# CameraController.net
KiCad netlist of a schematic drawn in EAGLE
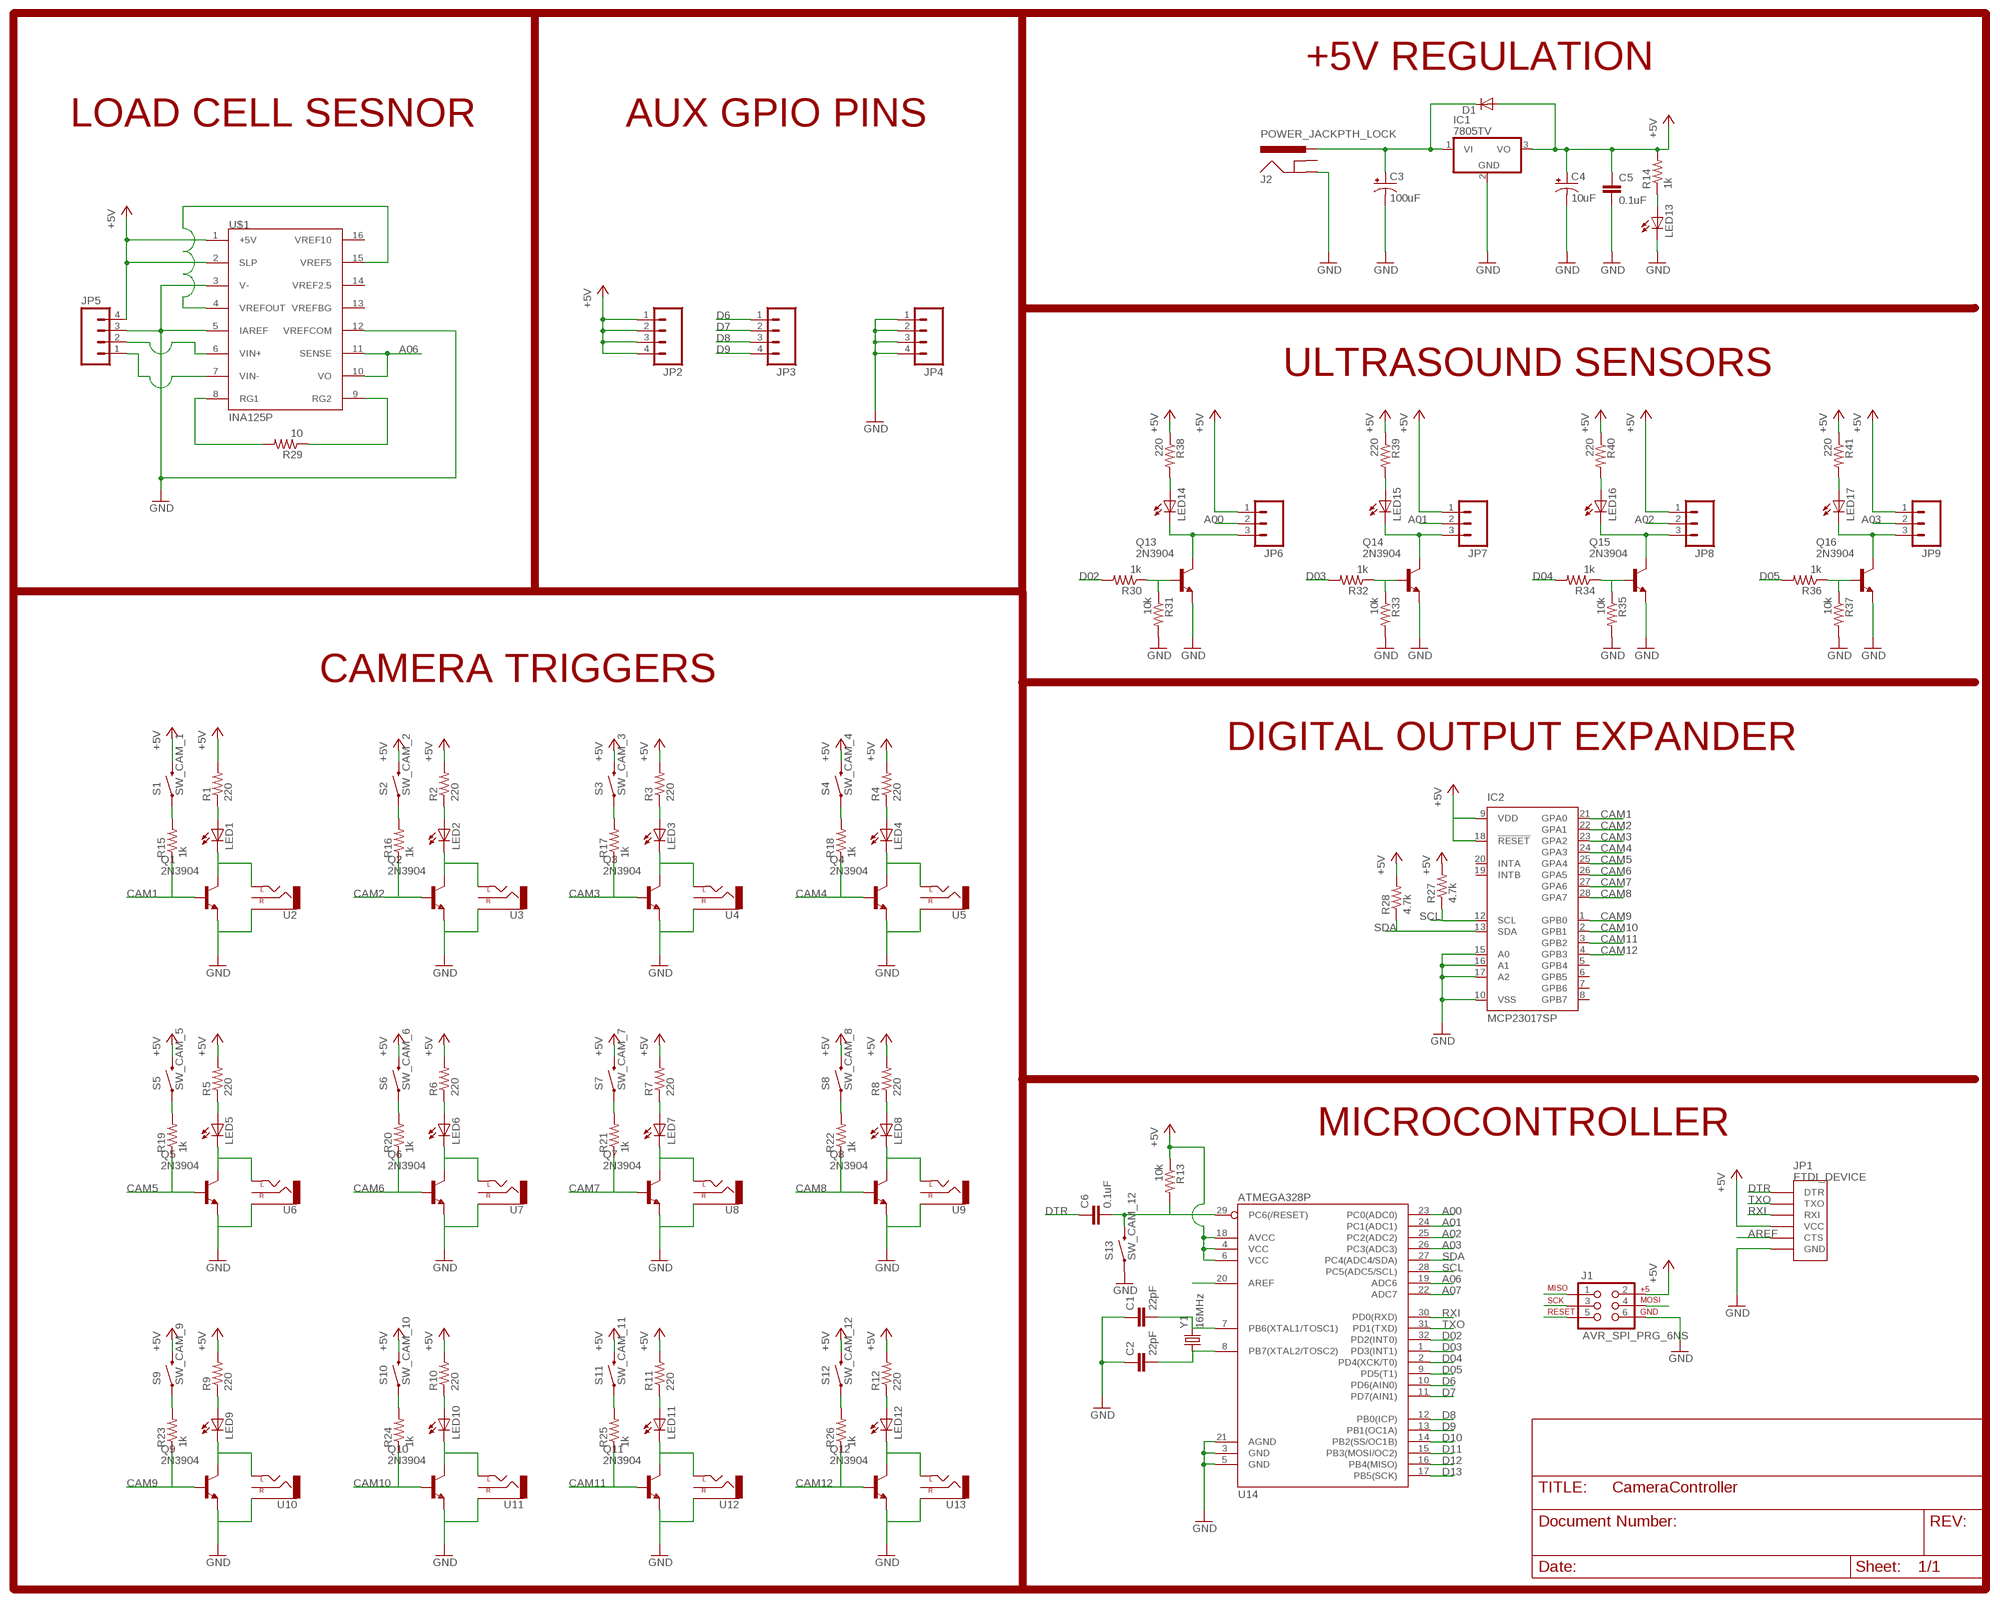
[diagram p0: schematic, sheet 1]

(export (version "E")
  (design (tool "Eeschema 10.0.6"))
  (components
    (comp (ref "C1")
      (value "22pF")
      (footprint "eagle-import:CAP-PTH-SMALL2")
      (libsource (lib "eagle-import") (part "CAPPTH2"))
    )
    (comp (ref "C2")
      (value "22pF")
      (footprint "eagle-import:CAP-PTH-SMALL2")
      (libsource (lib "eagle-import") (part "CAPPTH2"))
    )
    (comp (ref "C3")
      (value "100uF")
      (footprint "eagle-import:E2,5-7")
      (libsource (lib "eagle-import") (part "CPOL-USE2.5-7"))
    )
    (comp (ref "C4")
      (value "10uF")
      (footprint "eagle-import:E2,5-5")
      (libsource (lib "eagle-import") (part "CPOL-USE2.5-5"))
    )
    (comp (ref "C5")
      (value "0.1uF")
      (footprint "eagle-import:C025-025X050")
      (libsource (lib "eagle-import") (part "C-EU025-025X050"))
    )
    (comp (ref "C6")
      (value "0.1uF")
      (footprint "eagle-import:C025-025X050")
      (libsource (lib "eagle-import") (part "C-EU025-025X050"))
    )
    (comp (ref "D1")
      (value "DIODEPTH")
      (footprint "eagle-import:DIODE-1N4001")
      (libsource (lib "eagle-import") (part "DIODEPTH"))
    )
    (comp (ref "IC1")
      (value "7805TV")
      (footprint "eagle-import:TO220V")
      (libsource (lib "eagle-import") (part "78TV05"))
    )
    (comp (ref "IC2")
      (value "MCP23017SP")
      (footprint "eagle-import:DIL28-3")
      (libsource (lib "eagle-import") (part "MCP23017SP"))
    )
    (comp (ref "J1")
      (value "AVR_SPI_PRG_6NS")
      (footprint "eagle-import:2X3-NS")
      (libsource (lib "eagle-import") (part "AVR_SPI_PRG_6NS"))
    )
    (comp (ref "J2")
      (value "POWER_JACKPTH_LOCK")
      (footprint "eagle-import:POWER_JACK_PTH_LOCK")
      (libsource (lib "eagle-import") (part "POWER_JACKPTH_LOCK"))
    )
    (comp (ref "JP1")
      (value "FTDI_DEVICE")
      (footprint "eagle-import:FTDI_DEVICE_SIDE")
      (libsource (lib "eagle-import") (part "FTDI_DEVICE"))
    )
    (comp (ref "JP2")
      (value "M04PTH")
      (footprint "eagle-import:1X04")
      (libsource (lib "eagle-import") (part "M04PTH"))
    )
    (comp (ref "JP3")
      (value "M04PTH")
      (footprint "eagle-import:1X04")
      (libsource (lib "eagle-import") (part "M04PTH"))
    )
    (comp (ref "JP4")
      (value "M04PTH")
      (footprint "eagle-import:1X04")
      (libsource (lib "eagle-import") (part "M04PTH"))
    )
    (comp (ref "JP5")
      (value "M04LONGPADS")
      (footprint "eagle-import:1X04_LONGPADS")
      (libsource (lib "eagle-import") (part "M04LONGPADS"))
    )
    (comp (ref "JP6")
      (value "M03LONGPADS")
      (footprint "eagle-import:1X03_LONGPADS")
      (libsource (lib "eagle-import") (part "M03LONGPADS"))
    )
    (comp (ref "JP7")
      (value "M03LONGPADS")
      (footprint "eagle-import:1X03_LONGPADS")
      (libsource (lib "eagle-import") (part "M03LONGPADS"))
    )
    (comp (ref "JP8")
      (value "M03LONGPADS")
      (footprint "eagle-import:1X03_LONGPADS")
      (libsource (lib "eagle-import") (part "M03LONGPADS"))
    )
    (comp (ref "JP9")
      (value "M03LONGPADS")
      (footprint "eagle-import:1X03_LONGPADS")
      (libsource (lib "eagle-import") (part "M03LONGPADS"))
    )
    (comp (ref "LED1")
      (value "LED5MM")
      (footprint "eagle-import:LED5MM")
      (libsource (lib "eagle-import") (part "LED5MM"))
    )
    (comp (ref "LED2")
      (value "LED5MM")
      (footprint "eagle-import:LED5MM")
      (libsource (lib "eagle-import") (part "LED5MM"))
    )
    (comp (ref "LED3")
      (value "LED5MM")
      (footprint "eagle-import:LED5MM")
      (libsource (lib "eagle-import") (part "LED5MM"))
    )
    (comp (ref "LED4")
      (value "LED5MM")
      (footprint "eagle-import:LED5MM")
      (libsource (lib "eagle-import") (part "LED5MM"))
    )
    (comp (ref "LED5")
      (value "LED5MM")
      (footprint "eagle-import:LED5MM")
      (libsource (lib "eagle-import") (part "LED5MM"))
    )
    (comp (ref "LED6")
      (value "LED5MM")
      (footprint "eagle-import:LED5MM")
      (libsource (lib "eagle-import") (part "LED5MM"))
    )
    (comp (ref "LED7")
      (value "LED5MM")
      (footprint "eagle-import:LED5MM")
      (libsource (lib "eagle-import") (part "LED5MM"))
    )
    (comp (ref "LED8")
      (value "LED5MM")
      (footprint "eagle-import:LED5MM")
      (libsource (lib "eagle-import") (part "LED5MM"))
    )
    (comp (ref "LED9")
      (value "LED5MM")
      (footprint "eagle-import:LED5MM")
      (libsource (lib "eagle-import") (part "LED5MM"))
    )
    (comp (ref "LED10")
      (value "LED5MM")
      (footprint "eagle-import:LED5MM")
      (libsource (lib "eagle-import") (part "LED5MM"))
    )
    (comp (ref "LED11")
      (value "LED5MM")
      (footprint "eagle-import:LED5MM")
      (libsource (lib "eagle-import") (part "LED5MM"))
    )
    (comp (ref "LED12")
      (value "LED5MM")
      (footprint "eagle-import:LED5MM")
      (libsource (lib "eagle-import") (part "LED5MM"))
    )
    (comp (ref "LED13")
      (value "LED5MM")
      (footprint "eagle-import:LED5MM")
      (libsource (lib "eagle-import") (part "LED5MM"))
    )
    (comp (ref "LED14")
      (value "LED5MM")
      (footprint "eagle-import:LED5MM")
      (libsource (lib "eagle-import") (part "LED5MM"))
    )
    (comp (ref "LED15")
      (value "LED5MM")
      (footprint "eagle-import:LED5MM")
      (libsource (lib "eagle-import") (part "LED5MM"))
    )
    (comp (ref "LED16")
      (value "LED5MM")
      (footprint "eagle-import:LED5MM")
      (libsource (lib "eagle-import") (part "LED5MM"))
    )
    (comp (ref "LED17")
      (value "LED5MM")
      (footprint "eagle-import:LED5MM")
      (libsource (lib "eagle-import") (part "LED5MM"))
    )
    (comp (ref "Q1")
      (value "2N3904")
      (footprint "eagle-import:TO92")
      (libsource (lib "eagle-import") (part "2N3904"))
    )
    (comp (ref "Q2")
      (value "2N3904")
      (footprint "eagle-import:TO92")
      (libsource (lib "eagle-import") (part "2N3904"))
    )
    (comp (ref "Q3")
      (value "2N3904")
      (footprint "eagle-import:TO92")
      (libsource (lib "eagle-import") (part "2N3904"))
    )
    (comp (ref "Q4")
      (value "2N3904")
      (footprint "eagle-import:TO92")
      (libsource (lib "eagle-import") (part "2N3904"))
    )
    (comp (ref "Q5")
      (value "2N3904")
      (footprint "eagle-import:TO92")
      (libsource (lib "eagle-import") (part "2N3904"))
    )
    (comp (ref "Q6")
      (value "2N3904")
      (footprint "eagle-import:TO92")
      (libsource (lib "eagle-import") (part "2N3904"))
    )
    (comp (ref "Q7")
      (value "2N3904")
      (footprint "eagle-import:TO92")
      (libsource (lib "eagle-import") (part "2N3904"))
    )
    (comp (ref "Q8")
      (value "2N3904")
      (footprint "eagle-import:TO92")
      (libsource (lib "eagle-import") (part "2N3904"))
    )
    (comp (ref "Q9")
      (value "2N3904")
      (footprint "eagle-import:TO92")
      (libsource (lib "eagle-import") (part "2N3904"))
    )
    (comp (ref "Q10")
      (value "2N3904")
      (footprint "eagle-import:TO92")
      (libsource (lib "eagle-import") (part "2N3904"))
    )
    (comp (ref "Q11")
      (value "2N3904")
      (footprint "eagle-import:TO92")
      (libsource (lib "eagle-import") (part "2N3904"))
    )
    (comp (ref "Q12")
      (value "2N3904")
      (footprint "eagle-import:TO92")
      (libsource (lib "eagle-import") (part "2N3904"))
    )
    (comp (ref "Q13")
      (value "2N3904")
      (footprint "eagle-import:TO92")
      (libsource (lib "eagle-import") (part "2N3904"))
    )
    (comp (ref "Q14")
      (value "2N3904")
      (footprint "eagle-import:TO92")
      (libsource (lib "eagle-import") (part "2N3904"))
    )
    (comp (ref "Q15")
      (value "2N3904")
      (footprint "eagle-import:TO92")
      (libsource (lib "eagle-import") (part "2N3904"))
    )
    (comp (ref "Q16")
      (value "2N3904")
      (footprint "eagle-import:TO92")
      (libsource (lib "eagle-import") (part "2N3904"))
    )
    (comp (ref "R1")
      (value "220")
      (footprint "eagle-import:0207_10")
      (libsource (lib "eagle-import") (part "R-US_0207/10"))
    )
    (comp (ref "R2")
      (value "220")
      (footprint "eagle-import:0207_10")
      (libsource (lib "eagle-import") (part "R-US_0207/10"))
    )
    (comp (ref "R3")
      (value "220")
      (footprint "eagle-import:0207_10")
      (libsource (lib "eagle-import") (part "R-US_0207/10"))
    )
    (comp (ref "R4")
      (value "220")
      (footprint "eagle-import:0207_10")
      (libsource (lib "eagle-import") (part "R-US_0207/10"))
    )
    (comp (ref "R5")
      (value "220")
      (footprint "eagle-import:0207_10")
      (libsource (lib "eagle-import") (part "R-US_0207/10"))
    )
    (comp (ref "R6")
      (value "220")
      (footprint "eagle-import:0207_10")
      (libsource (lib "eagle-import") (part "R-US_0207/10"))
    )
    (comp (ref "R7")
      (value "220")
      (footprint "eagle-import:0207_10")
      (libsource (lib "eagle-import") (part "R-US_0207/10"))
    )
    (comp (ref "R8")
      (value "220")
      (footprint "eagle-import:0207_10")
      (libsource (lib "eagle-import") (part "R-US_0207/10"))
    )
    (comp (ref "R9")
      (value "220")
      (footprint "eagle-import:0207_10")
      (libsource (lib "eagle-import") (part "R-US_0207/10"))
    )
    (comp (ref "R10")
      (value "220")
      (footprint "eagle-import:0207_10")
      (libsource (lib "eagle-import") (part "R-US_0207/10"))
    )
    (comp (ref "R11")
      (value "220")
      (footprint "eagle-import:0207_10")
      (libsource (lib "eagle-import") (part "R-US_0207/10"))
    )
    (comp (ref "R12")
      (value "220")
      (footprint "eagle-import:0207_10")
      (libsource (lib "eagle-import") (part "R-US_0207/10"))
    )
    (comp (ref "R13")
      (value "10k")
      (footprint "eagle-import:0207_10")
      (libsource (lib "eagle-import") (part "R-US_0207/10"))
    )
    (comp (ref "R14")
      (value "1k")
      (footprint "eagle-import:0207_10")
      (libsource (lib "eagle-import") (part "R-US_0207/10"))
    )
    (comp (ref "R15")
      (value "1k")
      (footprint "eagle-import:0207_10")
      (libsource (lib "eagle-import") (part "R-US_0207/10"))
    )
    (comp (ref "R16")
      (value "1k")
      (footprint "eagle-import:0207_10")
      (libsource (lib "eagle-import") (part "R-US_0207/10"))
    )
    (comp (ref "R17")
      (value "1k")
      (footprint "eagle-import:0207_10")
      (libsource (lib "eagle-import") (part "R-US_0207/10"))
    )
    (comp (ref "R18")
      (value "1k")
      (footprint "eagle-import:0207_10")
      (libsource (lib "eagle-import") (part "R-US_0207/10"))
    )
    (comp (ref "R19")
      (value "1k")
      (footprint "eagle-import:0207_10")
      (libsource (lib "eagle-import") (part "R-US_0207/10"))
    )
    (comp (ref "R20")
      (value "1k")
      (footprint "eagle-import:0207_10")
      (libsource (lib "eagle-import") (part "R-US_0207/10"))
    )
    (comp (ref "R21")
      (value "1k")
      (footprint "eagle-import:0207_10")
      (libsource (lib "eagle-import") (part "R-US_0207/10"))
    )
    (comp (ref "R22")
      (value "1k")
      (footprint "eagle-import:0207_10")
      (libsource (lib "eagle-import") (part "R-US_0207/10"))
    )
    (comp (ref "R23")
      (value "1k")
      (footprint "eagle-import:0207_10")
      (libsource (lib "eagle-import") (part "R-US_0207/10"))
    )
    (comp (ref "R24")
      (value "1k")
      (footprint "eagle-import:0207_10")
      (libsource (lib "eagle-import") (part "R-US_0207/10"))
    )
    (comp (ref "R25")
      (value "1k")
      (footprint "eagle-import:0207_10")
      (libsource (lib "eagle-import") (part "R-US_0207/10"))
    )
    (comp (ref "R26")
      (value "1k")
      (footprint "eagle-import:0207_10")
      (libsource (lib "eagle-import") (part "R-US_0207/10"))
    )
    (comp (ref "R27")
      (value "4.7k")
      (footprint "eagle-import:0207_10")
      (libsource (lib "eagle-import") (part "R-US_0207/10"))
    )
    (comp (ref "R28")
      (value "4.7k")
      (footprint "eagle-import:0207_10")
      (libsource (lib "eagle-import") (part "R-US_0207/10"))
    )
    (comp (ref "R29")
      (value "10")
      (footprint "eagle-import:0207_10")
      (libsource (lib "eagle-import") (part "R-US_0207/10"))
    )
    (comp (ref "R30")
      (value "1k")
      (footprint "eagle-import:0207_10")
      (libsource (lib "eagle-import") (part "R-US_0207/10"))
    )
    (comp (ref "R31")
      (value "10k")
      (footprint "eagle-import:0207_10")
      (libsource (lib "eagle-import") (part "R-US_0207/10"))
    )
    (comp (ref "R32")
      (value "1k")
      (footprint "eagle-import:0207_10")
      (libsource (lib "eagle-import") (part "R-US_0207/10"))
    )
    (comp (ref "R33")
      (value "10k")
      (footprint "eagle-import:0207_10")
      (libsource (lib "eagle-import") (part "R-US_0207/10"))
    )
    (comp (ref "R34")
      (value "1k")
      (footprint "eagle-import:0207_10")
      (libsource (lib "eagle-import") (part "R-US_0207/10"))
    )
    (comp (ref "R35")
      (value "10k")
      (footprint "eagle-import:0207_10")
      (libsource (lib "eagle-import") (part "R-US_0207/10"))
    )
    (comp (ref "R36")
      (value "1k")
      (footprint "eagle-import:0207_10")
      (libsource (lib "eagle-import") (part "R-US_0207/10"))
    )
    (comp (ref "R37")
      (value "10k")
      (footprint "eagle-import:0207_10")
      (libsource (lib "eagle-import") (part "R-US_0207/10"))
    )
    (comp (ref "R38")
      (value "220")
      (footprint "eagle-import:0207_10")
      (libsource (lib "eagle-import") (part "R-US_0207/10"))
    )
    (comp (ref "R39")
      (value "220")
      (footprint "eagle-import:0207_10")
      (libsource (lib "eagle-import") (part "R-US_0207/10"))
    )
    (comp (ref "R40")
      (value "220")
      (footprint "eagle-import:0207_10")
      (libsource (lib "eagle-import") (part "R-US_0207/10"))
    )
    (comp (ref "R41")
      (value "220")
      (footprint "eagle-import:0207_10")
      (libsource (lib "eagle-import") (part "R-US_0207/10"))
    )
    (comp (ref "S1")
      (value "SW_CAM_1")
      (footprint "eagle-import:TACTILE-PTH")
      (libsource (lib "eagle-import") (part "SWITCH-MOMENTARY-2PTH"))
    )
    (comp (ref "S2")
      (value "SW_CAM_2")
      (footprint "eagle-import:TACTILE-PTH")
      (libsource (lib "eagle-import") (part "SWITCH-MOMENTARY-2PTH"))
    )
    (comp (ref "S3")
      (value "SW_CAM_3")
      (footprint "eagle-import:TACTILE-PTH")
      (libsource (lib "eagle-import") (part "SWITCH-MOMENTARY-2PTH"))
    )
    (comp (ref "S4")
      (value "SW_CAM_4")
      (footprint "eagle-import:TACTILE-PTH")
      (libsource (lib "eagle-import") (part "SWITCH-MOMENTARY-2PTH"))
    )
    (comp (ref "S5")
      (value "SW_CAM_5")
      (footprint "eagle-import:TACTILE-PTH")
      (libsource (lib "eagle-import") (part "SWITCH-MOMENTARY-2PTH"))
    )
    (comp (ref "S6")
      (value "SW_CAM_6")
      (footprint "eagle-import:TACTILE-PTH")
      (libsource (lib "eagle-import") (part "SWITCH-MOMENTARY-2PTH"))
    )
    (comp (ref "S7")
      (value "SW_CAM_7")
      (footprint "eagle-import:TACTILE-PTH")
      (libsource (lib "eagle-import") (part "SWITCH-MOMENTARY-2PTH"))
    )
    (comp (ref "S8")
      (value "SW_CAM_8")
      (footprint "eagle-import:TACTILE-PTH")
      (libsource (lib "eagle-import") (part "SWITCH-MOMENTARY-2PTH"))
    )
    (comp (ref "S9")
      (value "SW_CAM_9")
      (footprint "eagle-import:TACTILE-PTH")
      (libsource (lib "eagle-import") (part "SWITCH-MOMENTARY-2PTH"))
    )
    (comp (ref "S10")
      (value "SW_CAM_10")
      (footprint "eagle-import:TACTILE-PTH")
      (libsource (lib "eagle-import") (part "SWITCH-MOMENTARY-2PTH"))
    )
    (comp (ref "S11")
      (value "SW_CAM_11")
      (footprint "eagle-import:TACTILE-PTH")
      (libsource (lib "eagle-import") (part "SWITCH-MOMENTARY-2PTH"))
    )
    (comp (ref "S12")
      (value "SW_CAM_12")
      (footprint "eagle-import:TACTILE-PTH")
      (libsource (lib "eagle-import") (part "SWITCH-MOMENTARY-2PTH"))
    )
    (comp (ref "S13")
      (value "SW_CAM_12")
      (footprint "eagle-import:TACTILE-PTH")
      (libsource (lib "eagle-import") (part "SWITCH-MOMENTARY-2PTH"))
    )
    (comp (ref "U$1")
      (value "INA125P")
      (footprint "eagle-import:16-DIP")
      (libsource (lib "eagle-import") (part "INA125P"))
    )
    (comp (ref "U2")
      (value "AUDIO-JACKSPECIAL_POGO_PINS")
      (footprint "eagle-import:STEREOJACK2.5MM_SPECIA_POGOPINS")
      (libsource (lib "eagle-import") (part "AUDIO-JACKSPECIAL_POGO_PINS"))
    )
    (comp (ref "U3")
      (value "AUDIO-JACKSPECIAL_POGO_PINS")
      (footprint "eagle-import:STEREOJACK2.5MM_SPECIA_POGOPINS")
      (libsource (lib "eagle-import") (part "AUDIO-JACKSPECIAL_POGO_PINS"))
    )
    (comp (ref "U4")
      (value "AUDIO-JACKSPECIAL_POGO_PINS")
      (footprint "eagle-import:STEREOJACK2.5MM_SPECIA_POGOPINS")
      (libsource (lib "eagle-import") (part "AUDIO-JACKSPECIAL_POGO_PINS"))
    )
    (comp (ref "U5")
      (value "AUDIO-JACKSPECIAL_POGO_PINS")
      (footprint "eagle-import:STEREOJACK2.5MM_SPECIA_POGOPINS")
      (libsource (lib "eagle-import") (part "AUDIO-JACKSPECIAL_POGO_PINS"))
    )
    (comp (ref "U6")
      (value "AUDIO-JACKSPECIAL_POGO_PINS")
      (footprint "eagle-import:STEREOJACK2.5MM_SPECIA_POGOPINS")
      (libsource (lib "eagle-import") (part "AUDIO-JACKSPECIAL_POGO_PINS"))
    )
    (comp (ref "U7")
      (value "AUDIO-JACKSPECIAL_POGO_PINS")
      (footprint "eagle-import:STEREOJACK2.5MM_SPECIA_POGOPINS")
      (libsource (lib "eagle-import") (part "AUDIO-JACKSPECIAL_POGO_PINS"))
    )
    (comp (ref "U8")
      (value "AUDIO-JACKSPECIAL_POGO_PINS")
      (footprint "eagle-import:STEREOJACK2.5MM_SPECIA_POGOPINS")
      (libsource (lib "eagle-import") (part "AUDIO-JACKSPECIAL_POGO_PINS"))
    )
    (comp (ref "U9")
      (value "AUDIO-JACKSPECIAL_POGO_PINS")
      (footprint "eagle-import:STEREOJACK2.5MM_SPECIA_POGOPINS")
      (libsource (lib "eagle-import") (part "AUDIO-JACKSPECIAL_POGO_PINS"))
    )
    (comp (ref "U10")
      (value "AUDIO-JACKSPECIAL_POGO_PINS")
      (footprint "eagle-import:STEREOJACK2.5MM_SPECIA_POGOPINS")
      (libsource (lib "eagle-import") (part "AUDIO-JACKSPECIAL_POGO_PINS"))
    )
    (comp (ref "U11")
      (value "AUDIO-JACKSPECIAL_POGO_PINS")
      (footprint "eagle-import:STEREOJACK2.5MM_SPECIA_POGOPINS")
      (libsource (lib "eagle-import") (part "AUDIO-JACKSPECIAL_POGO_PINS"))
    )
    (comp (ref "U12")
      (value "AUDIO-JACKSPECIAL_POGO_PINS")
      (footprint "eagle-import:STEREOJACK2.5MM_SPECIA_POGOPINS")
      (libsource (lib "eagle-import") (part "AUDIO-JACKSPECIAL_POGO_PINS"))
    )
    (comp (ref "U13")
      (value "AUDIO-JACKSPECIAL_POGO_PINS")
      (footprint "eagle-import:STEREOJACK2.5MM_SPECIA_POGOPINS")
      (libsource (lib "eagle-import") (part "AUDIO-JACKSPECIAL_POGO_PINS"))
    )
    (comp (ref "U14")
      (value "ATMEGA328P")
      (footprint "eagle-import:TQFP32-08")
      (libsource (lib "eagle-import") (part "ATMEGA328_SMT"))
    )
    (comp (ref "Y1")
      (value "16MHz")
      (footprint "eagle-import:HC49US")
      (libsource (lib "eagle-import") (part "CRYSTALHC49US"))
    )
  )
  (nets
    (net (code "1") (name "+5V") (class "Default")
      (node (ref "C4") (pin "+") (pinfunction "+_+") (pintype "passive"))
      (node (ref "C5") (pin "1") (pinfunction "1_1") (pintype "passive"))
      (node (ref "D1") (pin "A") (pinfunction "A_A") (pintype "passive"))
      (node (ref "IC1") (pin "3") (pinfunction "VO_3") (pintype "passive"))
      (node (ref "IC2") (pin "18") (pinfunction "~{RESET}_18") (pintype "input"))
      (node (ref "IC2") (pin "9") (pinfunction "VDD_9") (pintype "power_in"))
      (node (ref "J1") (pin "2") (pinfunction "2_2") (pintype "passive"))
      (node (ref "JP1") (pin "P$4") (pinfunction "VCC_P$4") (pintype "bidirectional"))
      (node (ref "JP2") (pin "1") (pinfunction "1_1") (pintype "passive"))
      (node (ref "JP2") (pin "2") (pinfunction "2_2") (pintype "passive"))
      (node (ref "JP2") (pin "3") (pinfunction "3_3") (pintype "passive"))
      (node (ref "JP2") (pin "4") (pinfunction "4_4") (pintype "passive"))
      (node (ref "JP5") (pin "4") (pinfunction "4_4") (pintype "passive"))
      (node (ref "JP6") (pin "1") (pinfunction "1_1") (pintype "passive"))
      (node (ref "JP7") (pin "1") (pinfunction "1_1") (pintype "passive"))
      (node (ref "JP8") (pin "1") (pinfunction "1_1") (pintype "passive"))
      (node (ref "JP9") (pin "1") (pinfunction "1_1") (pintype "passive"))
      (node (ref "R1") (pin "2") (pinfunction "2_2") (pintype "passive"))
      (node (ref "R10") (pin "2") (pinfunction "2_2") (pintype "passive"))
      (node (ref "R11") (pin "2") (pinfunction "2_2") (pintype "passive"))
      (node (ref "R12") (pin "2") (pinfunction "2_2") (pintype "passive"))
      (node (ref "R13") (pin "1") (pinfunction "1_1") (pintype "passive"))
      (node (ref "R14") (pin "2") (pinfunction "2_2") (pintype "passive"))
      (node (ref "R2") (pin "2") (pinfunction "2_2") (pintype "passive"))
      (node (ref "R27") (pin "2") (pinfunction "2_2") (pintype "passive"))
      (node (ref "R28") (pin "2") (pinfunction "2_2") (pintype "passive"))
      (node (ref "R3") (pin "2") (pinfunction "2_2") (pintype "passive"))
      (node (ref "R38") (pin "1") (pinfunction "1_1") (pintype "passive"))
      (node (ref "R39") (pin "1") (pinfunction "1_1") (pintype "passive"))
      (node (ref "R4") (pin "2") (pinfunction "2_2") (pintype "passive"))
      (node (ref "R40") (pin "1") (pinfunction "1_1") (pintype "passive"))
      (node (ref "R41") (pin "1") (pinfunction "1_1") (pintype "passive"))
      (node (ref "R5") (pin "2") (pinfunction "2_2") (pintype "passive"))
      (node (ref "R6") (pin "2") (pinfunction "2_2") (pintype "passive"))
      (node (ref "R7") (pin "2") (pinfunction "2_2") (pintype "passive"))
      (node (ref "R8") (pin "2") (pinfunction "2_2") (pintype "passive"))
      (node (ref "R9") (pin "2") (pinfunction "2_2") (pintype "passive"))
      (node (ref "S1") (pin "3") (pinfunction "2_3") (pintype "passive"))
      (node (ref "S10") (pin "3") (pinfunction "2_3") (pintype "passive"))
      (node (ref "S11") (pin "3") (pinfunction "2_3") (pintype "passive"))
      (node (ref "S12") (pin "3") (pinfunction "2_3") (pintype "passive"))
      (node (ref "S2") (pin "3") (pinfunction "2_3") (pintype "passive"))
      (node (ref "S3") (pin "3") (pinfunction "2_3") (pintype "passive"))
      (node (ref "S4") (pin "3") (pinfunction "2_3") (pintype "passive"))
      (node (ref "S5") (pin "3") (pinfunction "2_3") (pintype "passive"))
      (node (ref "S6") (pin "3") (pinfunction "2_3") (pintype "passive"))
      (node (ref "S7") (pin "3") (pinfunction "2_3") (pintype "passive"))
      (node (ref "S8") (pin "3") (pinfunction "2_3") (pintype "passive"))
      (node (ref "S9") (pin "3") (pinfunction "2_3") (pintype "passive"))
      (node (ref "U$1") (pin "1") (pinfunction "+5V_1") (pintype "bidirectional"))
      (node (ref "U$1") (pin "2") (pinfunction "SLP_2") (pintype "bidirectional"))
      (node (ref "U14") (pin "18") (pinfunction "AVCC_18") (pintype "bidirectional"))
      (node (ref "U14") (pin "4") (pinfunction "VCC_4") (pintype "bidirectional"))
      (node (ref "U14") (pin "6") (pinfunction "VCC_6") (pintype "bidirectional"))
    )
    (net (code "2") (name "/A00") (class "Default")
      (node (ref "JP6") (pin "2") (pinfunction "2_2") (pintype "passive"))
      (node (ref "U14") (pin "23") (pinfunction "PC0(ADC0)_23") (pintype "bidirectional"))
    )
    (net (code "3") (name "/A01") (class "Default")
      (node (ref "JP7") (pin "2") (pinfunction "2_2") (pintype "passive"))
      (node (ref "U14") (pin "24") (pinfunction "PC1(ADC1)_24") (pintype "bidirectional"))
    )
    (net (code "4") (name "/A02") (class "Default")
      (node (ref "JP8") (pin "2") (pinfunction "2_2") (pintype "passive"))
      (node (ref "U14") (pin "25") (pinfunction "PC2(ADC2)_25") (pintype "bidirectional"))
    )
    (net (code "5") (name "/A03") (class "Default")
      (node (ref "JP9") (pin "2") (pinfunction "2_2") (pintype "passive"))
      (node (ref "U14") (pin "26") (pinfunction "PC3(ADC3)_26") (pintype "bidirectional"))
    )
    (net (code "6") (name "/A06") (class "Default")
      (node (ref "U$1") (pin "10") (pinfunction "VO_10") (pintype "bidirectional"))
      (node (ref "U$1") (pin "11") (pinfunction "SENSE_11") (pintype "bidirectional"))
      (node (ref "U14") (pin "19") (pinfunction "ADC6_19") (pintype "bidirectional"))
    )
    (net (code "7") (name "/A07") (class "Default")
      (node (ref "U14") (pin "22") (pinfunction "ADC7_22") (pintype "bidirectional"))
    )
    (net (code "8") (name "/AREF") (class "Default")
      (node (ref "JP1") (pin "P$5") (pinfunction "CTS_P$5") (pintype "bidirectional"))
      (node (ref "U14") (pin "20") (pinfunction "AREF_20") (pintype "bidirectional"))
    )
    (net (code "9") (name "/CAM1") (class "Default")
      (node (ref "IC2") (pin "21") (pinfunction "GPA0_21") (pintype "bidirectional"))
      (node (ref "Q1") (pin "2") (pinfunction "B_2") (pintype "passive"))
      (node (ref "R15") (pin "1") (pinfunction "1_1") (pintype "passive"))
    )
    (net (code "10") (name "/CAM2") (class "Default")
      (node (ref "IC2") (pin "22") (pinfunction "GPA1_22") (pintype "bidirectional"))
      (node (ref "Q2") (pin "2") (pinfunction "B_2") (pintype "passive"))
      (node (ref "R16") (pin "1") (pinfunction "1_1") (pintype "passive"))
    )
    (net (code "11") (name "/CAM3") (class "Default")
      (node (ref "IC2") (pin "23") (pinfunction "GPA2_23") (pintype "bidirectional"))
      (node (ref "Q3") (pin "2") (pinfunction "B_2") (pintype "passive"))
      (node (ref "R17") (pin "1") (pinfunction "1_1") (pintype "passive"))
    )
    (net (code "12") (name "/CAM4") (class "Default")
      (node (ref "IC2") (pin "24") (pinfunction "GPA3_24") (pintype "bidirectional"))
      (node (ref "Q4") (pin "2") (pinfunction "B_2") (pintype "passive"))
      (node (ref "R18") (pin "1") (pinfunction "1_1") (pintype "passive"))
    )
    (net (code "13") (name "/CAM5") (class "Default")
      (node (ref "IC2") (pin "25") (pinfunction "GPA4_25") (pintype "bidirectional"))
      (node (ref "Q5") (pin "2") (pinfunction "B_2") (pintype "passive"))
      (node (ref "R19") (pin "1") (pinfunction "1_1") (pintype "passive"))
    )
    (net (code "14") (name "/CAM6") (class "Default")
      (node (ref "IC2") (pin "26") (pinfunction "GPA5_26") (pintype "bidirectional"))
      (node (ref "Q6") (pin "2") (pinfunction "B_2") (pintype "passive"))
      (node (ref "R20") (pin "1") (pinfunction "1_1") (pintype "passive"))
    )
    (net (code "15") (name "/CAM7") (class "Default")
      (node (ref "IC2") (pin "27") (pinfunction "GPA6_27") (pintype "bidirectional"))
      (node (ref "Q7") (pin "2") (pinfunction "B_2") (pintype "passive"))
      (node (ref "R21") (pin "1") (pinfunction "1_1") (pintype "passive"))
    )
    (net (code "16") (name "/CAM8") (class "Default")
      (node (ref "IC2") (pin "28") (pinfunction "GPA7_28") (pintype "bidirectional"))
      (node (ref "Q8") (pin "2") (pinfunction "B_2") (pintype "passive"))
      (node (ref "R22") (pin "1") (pinfunction "1_1") (pintype "passive"))
    )
    (net (code "17") (name "/CAM9") (class "Default")
      (node (ref "IC2") (pin "1") (pinfunction "GPB0_1") (pintype "bidirectional"))
      (node (ref "Q9") (pin "2") (pinfunction "B_2") (pintype "passive"))
      (node (ref "R23") (pin "1") (pinfunction "1_1") (pintype "passive"))
    )
    (net (code "18") (name "/CAM10") (class "Default")
      (node (ref "IC2") (pin "2") (pinfunction "GPB1_2") (pintype "bidirectional"))
      (node (ref "Q10") (pin "2") (pinfunction "B_2") (pintype "passive"))
      (node (ref "R24") (pin "1") (pinfunction "1_1") (pintype "passive"))
    )
    (net (code "19") (name "/CAM11") (class "Default")
      (node (ref "IC2") (pin "3") (pinfunction "GPB2_3") (pintype "bidirectional"))
      (node (ref "Q11") (pin "2") (pinfunction "B_2") (pintype "passive"))
      (node (ref "R25") (pin "1") (pinfunction "1_1") (pintype "passive"))
    )
    (net (code "20") (name "/CAM12") (class "Default")
      (node (ref "IC2") (pin "4") (pinfunction "GPB3_4") (pintype "bidirectional"))
      (node (ref "Q12") (pin "2") (pinfunction "B_2") (pintype "passive"))
      (node (ref "R26") (pin "1") (pinfunction "1_1") (pintype "passive"))
    )
    (net (code "21") (name "/D02") (class "Default")
      (node (ref "R30") (pin "2") (pinfunction "2_2") (pintype "passive"))
      (node (ref "U14") (pin "32") (pinfunction "PD2(INT0)_32") (pintype "bidirectional"))
    )
    (net (code "22") (name "/D03") (class "Default")
      (node (ref "R32") (pin "2") (pinfunction "2_2") (pintype "passive"))
      (node (ref "U14") (pin "1") (pinfunction "PD3(INT1)_1") (pintype "bidirectional"))
    )
    (net (code "23") (name "/D04") (class "Default")
      (node (ref "R34") (pin "2") (pinfunction "2_2") (pintype "passive"))
      (node (ref "U14") (pin "2") (pinfunction "PD4(XCK/T0)_2") (pintype "bidirectional"))
    )
    (net (code "24") (name "/D05") (class "Default")
      (node (ref "R36") (pin "2") (pinfunction "2_2") (pintype "passive"))
      (node (ref "U14") (pin "9") (pinfunction "PD5(T1)_9") (pintype "bidirectional"))
    )
    (net (code "25") (name "/D6") (class "Default")
      (node (ref "JP3") (pin "1") (pinfunction "1_1") (pintype "passive"))
      (node (ref "U14") (pin "10") (pinfunction "PD6(AIN0)_10") (pintype "bidirectional"))
    )
    (net (code "26") (name "/D7") (class "Default")
      (node (ref "JP3") (pin "2") (pinfunction "2_2") (pintype "passive"))
      (node (ref "U14") (pin "11") (pinfunction "PD7(AIN1)_11") (pintype "bidirectional"))
    )
    (net (code "27") (name "/D8") (class "Default")
      (node (ref "JP3") (pin "3") (pinfunction "3_3") (pintype "passive"))
      (node (ref "U14") (pin "12") (pinfunction "PB0(ICP)_12") (pintype "bidirectional"))
    )
    (net (code "28") (name "/D9") (class "Default")
      (node (ref "JP3") (pin "4") (pinfunction "4_4") (pintype "passive"))
      (node (ref "U14") (pin "13") (pinfunction "PB1(OC1A)_13") (pintype "bidirectional"))
    )
    (net (code "29") (name "/D10") (class "Default")
      (node (ref "U14") (pin "14") (pinfunction "PB2(SS/OC1B)_14") (pintype "bidirectional"))
    )
    (net (code "30") (name "/D11") (class "Default")
      (node (ref "J1") (pin "4") (pinfunction "4_4") (pintype "passive"))
      (node (ref "U14") (pin "15") (pinfunction "PB3(MOSI/OC2)_15") (pintype "bidirectional"))
    )
    (net (code "31") (name "/D12") (class "Default")
      (node (ref "J1") (pin "1") (pinfunction "1_1") (pintype "passive"))
      (node (ref "U14") (pin "16") (pinfunction "PB4(MISO)_16") (pintype "bidirectional"))
    )
    (net (code "32") (name "/D13") (class "Default")
      (node (ref "J1") (pin "3") (pinfunction "3_3") (pintype "passive"))
      (node (ref "U14") (pin "17") (pinfunction "PB5(SCK)_17") (pintype "bidirectional"))
    )
    (net (code "33") (name "/DTR") (class "Default")
      (node (ref "C6") (pin "1") (pinfunction "1_1") (pintype "passive"))
      (node (ref "JP1") (pin "P$1") (pinfunction "DTR_P$1") (pintype "bidirectional"))
    )
    (net (code "34") (name "/RST") (class "Default")
      (node (ref "C6") (pin "2") (pinfunction "2_2") (pintype "passive"))
      (node (ref "J1") (pin "5") (pinfunction "5_5") (pintype "passive"))
      (node (ref "R13") (pin "2") (pinfunction "2_2") (pintype "passive"))
      (node (ref "S13") (pin "3") (pinfunction "2_3") (pintype "passive"))
      (node (ref "U14") (pin "29") (pinfunction "PC6(/RESET)_29") (pintype "bidirectional"))
    )
    (net (code "35") (name "/RXI") (class "Default")
      (node (ref "JP1") (pin "P$3") (pinfunction "RXI_P$3") (pintype "bidirectional"))
      (node (ref "U14") (pin "30") (pinfunction "PD0(RXD)_30") (pintype "bidirectional"))
    )
    (net (code "36") (name "/SCL") (class "Default")
      (node (ref "IC2") (pin "12") (pinfunction "SCL_12") (pintype "input"))
      (node (ref "R27") (pin "1") (pinfunction "1_1") (pintype "passive"))
      (node (ref "U14") (pin "28") (pinfunction "PC5(ADC5/SCL)_28") (pintype "bidirectional"))
    )
    (net (code "37") (name "/SDA") (class "Default")
      (node (ref "IC2") (pin "13") (pinfunction "SDA_13") (pintype "bidirectional"))
      (node (ref "R28") (pin "1") (pinfunction "1_1") (pintype "passive"))
      (node (ref "U14") (pin "27") (pinfunction "PC4(ADC4/SDA)_27") (pintype "bidirectional"))
    )
    (net (code "38") (name "/TXO") (class "Default")
      (node (ref "JP1") (pin "P$2") (pinfunction "TXO_P$2") (pintype "bidirectional"))
      (node (ref "U14") (pin "31") (pinfunction "PD1(TXD)_31") (pintype "bidirectional"))
    )
    (net (code "39") (name "GND") (class "Default")
      (node (ref "C1") (pin "1") (pinfunction "1_1") (pintype "passive"))
      (node (ref "C2") (pin "1") (pinfunction "1_1") (pintype "passive"))
      (node (ref "C3") (pin "-") (pinfunction "-_-") (pintype "passive"))
      (node (ref "C4") (pin "-") (pinfunction "-_-") (pintype "passive"))
      (node (ref "C5") (pin "2") (pinfunction "2_2") (pintype "passive"))
      (node (ref "IC1") (pin "2") (pinfunction "GND_2") (pintype "passive"))
      (node (ref "IC2") (pin "10") (pinfunction "VSS_10") (pintype "power_in"))
      (node (ref "IC2") (pin "15") (pinfunction "A0_15") (pintype "input"))
      (node (ref "IC2") (pin "16") (pinfunction "A1_16") (pintype "input"))
      (node (ref "IC2") (pin "17") (pinfunction "A2_17") (pintype "input"))
      (node (ref "J1") (pin "6") (pinfunction "6_6") (pintype "passive"))
      (node (ref "J2") (pin "GND") (pinfunction "GND_GND") (pintype "bidirectional"))
      (node (ref "JP1") (pin "P$6") (pinfunction "GND_P$6") (pintype "bidirectional"))
      (node (ref "JP4") (pin "1") (pinfunction "1_1") (pintype "passive"))
      (node (ref "JP4") (pin "2") (pinfunction "2_2") (pintype "passive"))
      (node (ref "JP4") (pin "3") (pinfunction "3_3") (pintype "passive"))
      (node (ref "JP4") (pin "4") (pinfunction "4_4") (pintype "passive"))
      (node (ref "JP5") (pin "3") (pinfunction "3_3") (pintype "passive"))
      (node (ref "LED13") (pin "K") (pinfunction "C_K") (pintype "passive"))
      (node (ref "Q1") (pin "3") (pinfunction "E_3") (pintype "passive"))
      (node (ref "Q10") (pin "3") (pinfunction "E_3") (pintype "passive"))
      (node (ref "Q11") (pin "3") (pinfunction "E_3") (pintype "passive"))
      (node (ref "Q12") (pin "3") (pinfunction "E_3") (pintype "passive"))
      (node (ref "Q13") (pin "3") (pinfunction "E_3") (pintype "passive"))
      (node (ref "Q14") (pin "3") (pinfunction "E_3") (pintype "passive"))
      (node (ref "Q15") (pin "3") (pinfunction "E_3") (pintype "passive"))
      (node (ref "Q16") (pin "3") (pinfunction "E_3") (pintype "passive"))
      (node (ref "Q2") (pin "3") (pinfunction "E_3") (pintype "passive"))
      (node (ref "Q3") (pin "3") (pinfunction "E_3") (pintype "passive"))
      (node (ref "Q4") (pin "3") (pinfunction "E_3") (pintype "passive"))
      (node (ref "Q5") (pin "3") (pinfunction "E_3") (pintype "passive"))
      (node (ref "Q6") (pin "3") (pinfunction "E_3") (pintype "passive"))
      (node (ref "Q7") (pin "3") (pinfunction "E_3") (pintype "passive"))
      (node (ref "Q8") (pin "3") (pinfunction "E_3") (pintype "passive"))
      (node (ref "Q9") (pin "3") (pinfunction "E_3") (pintype "passive"))
      (node (ref "R31") (pin "2") (pinfunction "2_2") (pintype "passive"))
      (node (ref "R33") (pin "2") (pinfunction "2_2") (pintype "passive"))
      (node (ref "R35") (pin "2") (pinfunction "2_2") (pintype "passive"))
      (node (ref "R37") (pin "2") (pinfunction "2_2") (pintype "passive"))
      (node (ref "S13") (pin "1") (pinfunction "1_1") (pintype "passive"))
      (node (ref "U$1") (pin "12") (pinfunction "VREFCOM_12") (pintype "bidirectional"))
      (node (ref "U$1") (pin "3") (pinfunction "V-_3") (pintype "bidirectional"))
      (node (ref "U$1") (pin "5") (pinfunction "IAREF_5") (pintype "bidirectional"))
      (node (ref "U10") (pin "RING1") (pinfunction "SLEEVE_RING1") (pintype "bidirectional"))
      (node (ref "U11") (pin "RING1") (pinfunction "SLEEVE_RING1") (pintype "bidirectional"))
      (node (ref "U12") (pin "RING1") (pinfunction "SLEEVE_RING1") (pintype "bidirectional"))
      (node (ref "U13") (pin "RING1") (pinfunction "SLEEVE_RING1") (pintype "bidirectional"))
      (node (ref "U14") (pin "21") (pinfunction "AGND_21") (pintype "bidirectional"))
      (node (ref "U14") (pin "3") (pinfunction "GND_3") (pintype "bidirectional"))
      (node (ref "U14") (pin "5") (pinfunction "GND_5") (pintype "bidirectional"))
      (node (ref "U2") (pin "RING1") (pinfunction "SLEEVE_RING1") (pintype "bidirectional"))
      (node (ref "U3") (pin "RING1") (pinfunction "SLEEVE_RING1") (pintype "bidirectional"))
      (node (ref "U4") (pin "RING1") (pinfunction "SLEEVE_RING1") (pintype "bidirectional"))
      (node (ref "U5") (pin "RING1") (pinfunction "SLEEVE_RING1") (pintype "bidirectional"))
      (node (ref "U6") (pin "RING1") (pinfunction "SLEEVE_RING1") (pintype "bidirectional"))
      (node (ref "U7") (pin "RING1") (pinfunction "SLEEVE_RING1") (pintype "bidirectional"))
      (node (ref "U8") (pin "RING1") (pinfunction "SLEEVE_RING1") (pintype "bidirectional"))
      (node (ref "U9") (pin "RING1") (pinfunction "SLEEVE_RING1") (pintype "bidirectional"))
    )
    (net (code "40") (name "Net-(IC1-VI)") (class "Default")
      (node (ref "C3") (pin "+") (pinfunction "+_+") (pintype "passive"))
      (node (ref "D1") (pin "C") (pinfunction "C_C") (pintype "passive"))
      (node (ref "IC1") (pin "1") (pinfunction "VI_1") (pintype "input"))
      (node (ref "J2") (pin "PWR") (pinfunction "PWR_PWR") (pintype "bidirectional"))
    )
    (net (code "41") (name "Net-(LED1-C)") (class "Default")
      (node (ref "LED1") (pin "K") (pinfunction "C_K") (pintype "passive"))
      (node (ref "Q1") (pin "1") (pinfunction "C_1") (pintype "passive"))
      (node (ref "U2") (pin "SHIELD") (pinfunction "LEFT_SHIELD") (pintype "bidirectional"))
    )
    (net (code "42") (name "Net-(LED1-PadA)") (class "Default")
      (node (ref "LED1") (pin "A") (pinfunction "A_A") (pintype "passive"))
      (node (ref "R1") (pin "1") (pinfunction "1_1") (pintype "passive"))
    )
    (net (code "43") (name "Net-(LED2-C)") (class "Default")
      (node (ref "LED2") (pin "K") (pinfunction "C_K") (pintype "passive"))
      (node (ref "Q2") (pin "1") (pinfunction "C_1") (pintype "passive"))
      (node (ref "U3") (pin "SHIELD") (pinfunction "LEFT_SHIELD") (pintype "bidirectional"))
    )
    (net (code "44") (name "Net-(LED2-PadA)") (class "Default")
      (node (ref "LED2") (pin "A") (pinfunction "A_A") (pintype "passive"))
      (node (ref "R2") (pin "1") (pinfunction "1_1") (pintype "passive"))
    )
    (net (code "45") (name "Net-(LED3-C)") (class "Default")
      (node (ref "LED3") (pin "K") (pinfunction "C_K") (pintype "passive"))
      (node (ref "Q3") (pin "1") (pinfunction "C_1") (pintype "passive"))
      (node (ref "U4") (pin "SHIELD") (pinfunction "LEFT_SHIELD") (pintype "bidirectional"))
    )
    (net (code "46") (name "Net-(LED3-PadA)") (class "Default")
      (node (ref "LED3") (pin "A") (pinfunction "A_A") (pintype "passive"))
      (node (ref "R3") (pin "1") (pinfunction "1_1") (pintype "passive"))
    )
    (net (code "47") (name "Net-(LED4-C)") (class "Default")
      (node (ref "LED4") (pin "K") (pinfunction "C_K") (pintype "passive"))
      (node (ref "Q4") (pin "1") (pinfunction "C_1") (pintype "passive"))
      (node (ref "U5") (pin "SHIELD") (pinfunction "LEFT_SHIELD") (pintype "bidirectional"))
    )
    (net (code "48") (name "Net-(LED4-PadA)") (class "Default")
      (node (ref "LED4") (pin "A") (pinfunction "A_A") (pintype "passive"))
      (node (ref "R4") (pin "1") (pinfunction "1_1") (pintype "passive"))
    )
    (net (code "49") (name "Net-(LED5-C)") (class "Default")
      (node (ref "LED5") (pin "K") (pinfunction "C_K") (pintype "passive"))
      (node (ref "Q5") (pin "1") (pinfunction "C_1") (pintype "passive"))
      (node (ref "U6") (pin "SHIELD") (pinfunction "LEFT_SHIELD") (pintype "bidirectional"))
    )
    (net (code "50") (name "Net-(LED5-PadA)") (class "Default")
      (node (ref "LED5") (pin "A") (pinfunction "A_A") (pintype "passive"))
      (node (ref "R5") (pin "1") (pinfunction "1_1") (pintype "passive"))
    )
    (net (code "51") (name "Net-(LED6-C)") (class "Default")
      (node (ref "LED6") (pin "K") (pinfunction "C_K") (pintype "passive"))
      (node (ref "Q6") (pin "1") (pinfunction "C_1") (pintype "passive"))
      (node (ref "U7") (pin "SHIELD") (pinfunction "LEFT_SHIELD") (pintype "bidirectional"))
    )
    (net (code "52") (name "Net-(LED6-PadA)") (class "Default")
      (node (ref "LED6") (pin "A") (pinfunction "A_A") (pintype "passive"))
      (node (ref "R6") (pin "1") (pinfunction "1_1") (pintype "passive"))
    )
    (net (code "53") (name "Net-(LED7-C)") (class "Default")
      (node (ref "LED7") (pin "K") (pinfunction "C_K") (pintype "passive"))
      (node (ref "Q7") (pin "1") (pinfunction "C_1") (pintype "passive"))
      (node (ref "U8") (pin "SHIELD") (pinfunction "LEFT_SHIELD") (pintype "bidirectional"))
    )
    (net (code "54") (name "Net-(LED7-PadA)") (class "Default")
      (node (ref "LED7") (pin "A") (pinfunction "A_A") (pintype "passive"))
      (node (ref "R7") (pin "1") (pinfunction "1_1") (pintype "passive"))
    )
    (net (code "55") (name "Net-(LED8-C)") (class "Default")
      (node (ref "LED8") (pin "K") (pinfunction "C_K") (pintype "passive"))
      (node (ref "Q8") (pin "1") (pinfunction "C_1") (pintype "passive"))
      (node (ref "U9") (pin "SHIELD") (pinfunction "LEFT_SHIELD") (pintype "bidirectional"))
    )
    (net (code "56") (name "Net-(LED8-PadA)") (class "Default")
      (node (ref "LED8") (pin "A") (pinfunction "A_A") (pintype "passive"))
      (node (ref "R8") (pin "1") (pinfunction "1_1") (pintype "passive"))
    )
    (net (code "57") (name "Net-(LED9-C)") (class "Default")
      (node (ref "LED9") (pin "K") (pinfunction "C_K") (pintype "passive"))
      (node (ref "Q9") (pin "1") (pinfunction "C_1") (pintype "passive"))
      (node (ref "U10") (pin "SHIELD") (pinfunction "LEFT_SHIELD") (pintype "bidirectional"))
    )
    (net (code "58") (name "Net-(LED9-PadA)") (class "Default")
      (node (ref "LED9") (pin "A") (pinfunction "A_A") (pintype "passive"))
      (node (ref "R9") (pin "1") (pinfunction "1_1") (pintype "passive"))
    )
    (net (code "59") (name "Net-(LED10-C)") (class "Default")
      (node (ref "LED10") (pin "K") (pinfunction "C_K") (pintype "passive"))
      (node (ref "Q10") (pin "1") (pinfunction "C_1") (pintype "passive"))
      (node (ref "U11") (pin "SHIELD") (pinfunction "LEFT_SHIELD") (pintype "bidirectional"))
    )
    (net (code "60") (name "Net-(LED10-PadA)") (class "Default")
      (node (ref "LED10") (pin "A") (pinfunction "A_A") (pintype "passive"))
      (node (ref "R10") (pin "1") (pinfunction "1_1") (pintype "passive"))
    )
    (net (code "61") (name "Net-(LED11-C)") (class "Default")
      (node (ref "LED11") (pin "K") (pinfunction "C_K") (pintype "passive"))
      (node (ref "Q11") (pin "1") (pinfunction "C_1") (pintype "passive"))
      (node (ref "U12") (pin "SHIELD") (pinfunction "LEFT_SHIELD") (pintype "bidirectional"))
    )
    (net (code "62") (name "Net-(LED11-PadA)") (class "Default")
      (node (ref "LED11") (pin "A") (pinfunction "A_A") (pintype "passive"))
      (node (ref "R11") (pin "1") (pinfunction "1_1") (pintype "passive"))
    )
    (net (code "63") (name "Net-(LED12-C)") (class "Default")
      (node (ref "LED12") (pin "K") (pinfunction "C_K") (pintype "passive"))
      (node (ref "Q12") (pin "1") (pinfunction "C_1") (pintype "passive"))
      (node (ref "U13") (pin "SHIELD") (pinfunction "LEFT_SHIELD") (pintype "bidirectional"))
    )
    (net (code "64") (name "Net-(LED12-PadA)") (class "Default")
      (node (ref "LED12") (pin "A") (pinfunction "A_A") (pintype "passive"))
      (node (ref "R12") (pin "1") (pinfunction "1_1") (pintype "passive"))
    )
    (net (code "65") (name "Net-(LED13-PadA)") (class "Default")
      (node (ref "LED13") (pin "A") (pinfunction "A_A") (pintype "passive"))
      (node (ref "R14") (pin "1") (pinfunction "1_1") (pintype "passive"))
    )
    (net (code "66") (name "Net-(LED14-C)") (class "Default")
      (node (ref "JP6") (pin "3") (pinfunction "3_3") (pintype "passive"))
      (node (ref "LED14") (pin "K") (pinfunction "C_K") (pintype "passive"))
      (node (ref "Q13") (pin "1") (pinfunction "C_1") (pintype "passive"))
    )
    (net (code "67") (name "Net-(LED14-PadA)") (class "Default")
      (node (ref "LED14") (pin "A") (pinfunction "A_A") (pintype "passive"))
      (node (ref "R38") (pin "2") (pinfunction "2_2") (pintype "passive"))
    )
    (net (code "68") (name "Net-(LED15-C)") (class "Default")
      (node (ref "JP7") (pin "3") (pinfunction "3_3") (pintype "passive"))
      (node (ref "LED15") (pin "K") (pinfunction "C_K") (pintype "passive"))
      (node (ref "Q14") (pin "1") (pinfunction "C_1") (pintype "passive"))
    )
    (net (code "69") (name "Net-(LED15-PadA)") (class "Default")
      (node (ref "LED15") (pin "A") (pinfunction "A_A") (pintype "passive"))
      (node (ref "R39") (pin "2") (pinfunction "2_2") (pintype "passive"))
    )
    (net (code "70") (name "Net-(LED16-C)") (class "Default")
      (node (ref "JP8") (pin "3") (pinfunction "3_3") (pintype "passive"))
      (node (ref "LED16") (pin "K") (pinfunction "C_K") (pintype "passive"))
      (node (ref "Q15") (pin "1") (pinfunction "C_1") (pintype "passive"))
    )
    (net (code "71") (name "Net-(LED16-PadA)") (class "Default")
      (node (ref "LED16") (pin "A") (pinfunction "A_A") (pintype "passive"))
      (node (ref "R40") (pin "2") (pinfunction "2_2") (pintype "passive"))
    )
    (net (code "72") (name "Net-(LED17-C)") (class "Default")
      (node (ref "JP9") (pin "3") (pinfunction "3_3") (pintype "passive"))
      (node (ref "LED17") (pin "K") (pinfunction "C_K") (pintype "passive"))
      (node (ref "Q16") (pin "1") (pinfunction "C_1") (pintype "passive"))
    )
    (net (code "73") (name "Net-(LED17-PadA)") (class "Default")
      (node (ref "LED17") (pin "A") (pinfunction "A_A") (pintype "passive"))
      (node (ref "R41") (pin "2") (pinfunction "2_2") (pintype "passive"))
    )
    (net (code "74") (name "Net-(Q13-B)") (class "Default")
      (node (ref "Q13") (pin "2") (pinfunction "B_2") (pintype "passive"))
      (node (ref "R30") (pin "1") (pinfunction "1_1") (pintype "passive"))
      (node (ref "R31") (pin "1") (pinfunction "1_1") (pintype "passive"))
    )
    (net (code "75") (name "Net-(Q14-B)") (class "Default")
      (node (ref "Q14") (pin "2") (pinfunction "B_2") (pintype "passive"))
      (node (ref "R32") (pin "1") (pinfunction "1_1") (pintype "passive"))
      (node (ref "R33") (pin "1") (pinfunction "1_1") (pintype "passive"))
    )
    (net (code "76") (name "Net-(Q15-B)") (class "Default")
      (node (ref "Q15") (pin "2") (pinfunction "B_2") (pintype "passive"))
      (node (ref "R34") (pin "1") (pinfunction "1_1") (pintype "passive"))
      (node (ref "R35") (pin "1") (pinfunction "1_1") (pintype "passive"))
    )
    (net (code "77") (name "Net-(Q16-B)") (class "Default")
      (node (ref "Q16") (pin "2") (pinfunction "B_2") (pintype "passive"))
      (node (ref "R36") (pin "1") (pinfunction "1_1") (pintype "passive"))
      (node (ref "R37") (pin "1") (pinfunction "1_1") (pintype "passive"))
    )
    (net (code "78") (name "Net-(R15-Pad2)") (class "Default")
      (node (ref "R15") (pin "2") (pinfunction "2_2") (pintype "passive"))
      (node (ref "S1") (pin "1") (pinfunction "1_1") (pintype "passive"))
    )
    (net (code "79") (name "Net-(R16-Pad2)") (class "Default")
      (node (ref "R16") (pin "2") (pinfunction "2_2") (pintype "passive"))
      (node (ref "S2") (pin "1") (pinfunction "1_1") (pintype "passive"))
    )
    (net (code "80") (name "Net-(R17-Pad2)") (class "Default")
      (node (ref "R17") (pin "2") (pinfunction "2_2") (pintype "passive"))
      (node (ref "S3") (pin "1") (pinfunction "1_1") (pintype "passive"))
    )
    (net (code "81") (name "Net-(R18-Pad2)") (class "Default")
      (node (ref "R18") (pin "2") (pinfunction "2_2") (pintype "passive"))
      (node (ref "S4") (pin "1") (pinfunction "1_1") (pintype "passive"))
    )
    (net (code "82") (name "Net-(R19-Pad2)") (class "Default")
      (node (ref "R19") (pin "2") (pinfunction "2_2") (pintype "passive"))
      (node (ref "S5") (pin "1") (pinfunction "1_1") (pintype "passive"))
    )
    (net (code "83") (name "Net-(R20-Pad2)") (class "Default")
      (node (ref "R20") (pin "2") (pinfunction "2_2") (pintype "passive"))
      (node (ref "S6") (pin "1") (pinfunction "1_1") (pintype "passive"))
    )
    (net (code "84") (name "Net-(R21-Pad2)") (class "Default")
      (node (ref "R21") (pin "2") (pinfunction "2_2") (pintype "passive"))
      (node (ref "S7") (pin "1") (pinfunction "1_1") (pintype "passive"))
    )
    (net (code "85") (name "Net-(R22-Pad2)") (class "Default")
      (node (ref "R22") (pin "2") (pinfunction "2_2") (pintype "passive"))
      (node (ref "S8") (pin "1") (pinfunction "1_1") (pintype "passive"))
    )
    (net (code "86") (name "Net-(R23-Pad2)") (class "Default")
      (node (ref "R23") (pin "2") (pinfunction "2_2") (pintype "passive"))
      (node (ref "S9") (pin "1") (pinfunction "1_1") (pintype "passive"))
    )
    (net (code "87") (name "Net-(R24-Pad2)") (class "Default")
      (node (ref "R24") (pin "2") (pinfunction "2_2") (pintype "passive"))
      (node (ref "S10") (pin "1") (pinfunction "1_1") (pintype "passive"))
    )
    (net (code "88") (name "Net-(R25-Pad2)") (class "Default")
      (node (ref "R25") (pin "2") (pinfunction "2_2") (pintype "passive"))
      (node (ref "S11") (pin "1") (pinfunction "1_1") (pintype "passive"))
    )
    (net (code "89") (name "Net-(R26-Pad2)") (class "Default")
      (node (ref "R26") (pin "2") (pinfunction "2_2") (pintype "passive"))
      (node (ref "S12") (pin "1") (pinfunction "1_1") (pintype "passive"))
    )
    (net (code "90") (name "Net-(U$1-RG1)") (class "Default")
      (node (ref "R29") (pin "2") (pinfunction "2_2") (pintype "passive"))
      (node (ref "U$1") (pin "8") (pinfunction "RG1_8") (pintype "bidirectional"))
    )
    (net (code "91") (name "Net-(U$1-RG2)") (class "Default")
      (node (ref "R29") (pin "1") (pinfunction "1_1") (pintype "passive"))
      (node (ref "U$1") (pin "9") (pinfunction "RG2_9") (pintype "bidirectional"))
    )
    (net (code "92") (name "Net-(U$1-VIN+)") (class "Default")
      (node (ref "JP5") (pin "2") (pinfunction "2_2") (pintype "passive"))
      (node (ref "U$1") (pin "6") (pinfunction "VIN+_6") (pintype "bidirectional"))
    )
    (net (code "93") (name "Net-(U$1-VIN-)") (class "Default")
      (node (ref "JP5") (pin "1") (pinfunction "1_1") (pintype "passive"))
      (node (ref "U$1") (pin "7") (pinfunction "VIN-_7") (pintype "bidirectional"))
    )
    (net (code "94") (name "Net-(U$1-VREF5)") (class "Default")
      (node (ref "U$1") (pin "15") (pinfunction "VREF5_15") (pintype "bidirectional"))
      (node (ref "U$1") (pin "4") (pinfunction "VREFOUT_4") (pintype "bidirectional"))
    )
    (net (code "95") (name "Net-(U14-PB6(XTAL1{slash}TOSC1))") (class "Default")
      (node (ref "C1") (pin "2") (pinfunction "2_2") (pintype "passive"))
      (node (ref "U14") (pin "7") (pinfunction "PB6(XTAL1/TOSC1)_7") (pintype "bidirectional"))
      (node (ref "Y1") (pin "2") (pinfunction "2_2") (pintype "passive"))
    )
    (net (code "96") (name "Net-(U14-PB7(XTAL2{slash}TOSC2))") (class "Default")
      (node (ref "C2") (pin "2") (pinfunction "2_2") (pintype "passive"))
      (node (ref "U14") (pin "8") (pinfunction "PB7(XTAL2/TOSC2)_8") (pintype "bidirectional"))
      (node (ref "Y1") (pin "1") (pinfunction "1_1") (pintype "passive"))
    )
    (net (code "97") (name "unconnected-(IC2-GPB4-Pad5)") (class "Default")
      (node (ref "IC2") (pin "5") (pinfunction "GPB4_5") (pintype "bidirectional"))
    )
    (net (code "98") (name "unconnected-(IC2-GPB5-Pad6)") (class "Default")
      (node (ref "IC2") (pin "6") (pinfunction "GPB5_6") (pintype "bidirectional"))
    )
    (net (code "99") (name "unconnected-(IC2-GPB6-Pad7)") (class "Default")
      (node (ref "IC2") (pin "7") (pinfunction "GPB6_7") (pintype "bidirectional"))
    )
    (net (code "100") (name "unconnected-(IC2-GPB7-Pad8)") (class "Default")
      (node (ref "IC2") (pin "8") (pinfunction "GPB7_8") (pintype "bidirectional"))
    )
    (net (code "101") (name "unconnected-(IC2-INTA-Pad20)") (class "Default")
      (node (ref "IC2") (pin "20") (pinfunction "INTA_20") (pintype "output"))
    )
    (net (code "102") (name "unconnected-(IC2-INTB-Pad19)") (class "Default")
      (node (ref "IC2") (pin "19") (pinfunction "INTB_19") (pintype "output"))
    )
    (net (code "103") (name "unconnected-(J2-PadGNDBREAK)") (class "Default")
      (node (ref "J2") (pin "GNDBREAK") (pinfunction "GNDBREAK_GNDBREAK") (pintype "bidirectional"))
    )
    (net (code "104") (name "unconnected-(U$1-VREF2.5-Pad14)") (class "Default")
      (node (ref "U$1") (pin "14") (pinfunction "VREF2.5_14") (pintype "bidirectional"))
    )
    (net (code "105") (name "unconnected-(U$1-VREF10-Pad16)") (class "Default")
      (node (ref "U$1") (pin "16") (pinfunction "VREF10_16") (pintype "bidirectional"))
    )
    (net (code "106") (name "unconnected-(U$1-VREFBG-Pad13)") (class "Default")
      (node (ref "U$1") (pin "13") (pinfunction "VREFBG_13") (pintype "bidirectional"))
    )
    (net (code "107") (name "unconnected-(U2-RIGHT-PadTIP)") (class "Default")
      (node (ref "U2") (pin "TIP") (pinfunction "RIGHT_TIP") (pintype "bidirectional"))
    )
    (net (code "108") (name "unconnected-(U3-RIGHT-PadTIP)") (class "Default")
      (node (ref "U3") (pin "TIP") (pinfunction "RIGHT_TIP") (pintype "bidirectional"))
    )
    (net (code "109") (name "unconnected-(U4-RIGHT-PadTIP)") (class "Default")
      (node (ref "U4") (pin "TIP") (pinfunction "RIGHT_TIP") (pintype "bidirectional"))
    )
    (net (code "110") (name "unconnected-(U5-RIGHT-PadTIP)") (class "Default")
      (node (ref "U5") (pin "TIP") (pinfunction "RIGHT_TIP") (pintype "bidirectional"))
    )
    (net (code "111") (name "unconnected-(U6-RIGHT-PadTIP)") (class "Default")
      (node (ref "U6") (pin "TIP") (pinfunction "RIGHT_TIP") (pintype "bidirectional"))
    )
    (net (code "112") (name "unconnected-(U7-RIGHT-PadTIP)") (class "Default")
      (node (ref "U7") (pin "TIP") (pinfunction "RIGHT_TIP") (pintype "bidirectional"))
    )
    (net (code "113") (name "unconnected-(U8-RIGHT-PadTIP)") (class "Default")
      (node (ref "U8") (pin "TIP") (pinfunction "RIGHT_TIP") (pintype "bidirectional"))
    )
    (net (code "114") (name "unconnected-(U9-RIGHT-PadTIP)") (class "Default")
      (node (ref "U9") (pin "TIP") (pinfunction "RIGHT_TIP") (pintype "bidirectional"))
    )
    (net (code "115") (name "unconnected-(U10-RIGHT-PadTIP)") (class "Default")
      (node (ref "U10") (pin "TIP") (pinfunction "RIGHT_TIP") (pintype "bidirectional"))
    )
    (net (code "116") (name "unconnected-(U11-RIGHT-PadTIP)") (class "Default")
      (node (ref "U11") (pin "TIP") (pinfunction "RIGHT_TIP") (pintype "bidirectional"))
    )
    (net (code "117") (name "unconnected-(U12-RIGHT-PadTIP)") (class "Default")
      (node (ref "U12") (pin "TIP") (pinfunction "RIGHT_TIP") (pintype "bidirectional"))
    )
    (net (code "118") (name "unconnected-(U13-RIGHT-PadTIP)") (class "Default")
      (node (ref "U13") (pin "TIP") (pinfunction "RIGHT_TIP") (pintype "bidirectional"))
    )
  )
)
